# Dragon_LowerCase_v1.net
KiCad netlist of a schematic drawn in EAGLE
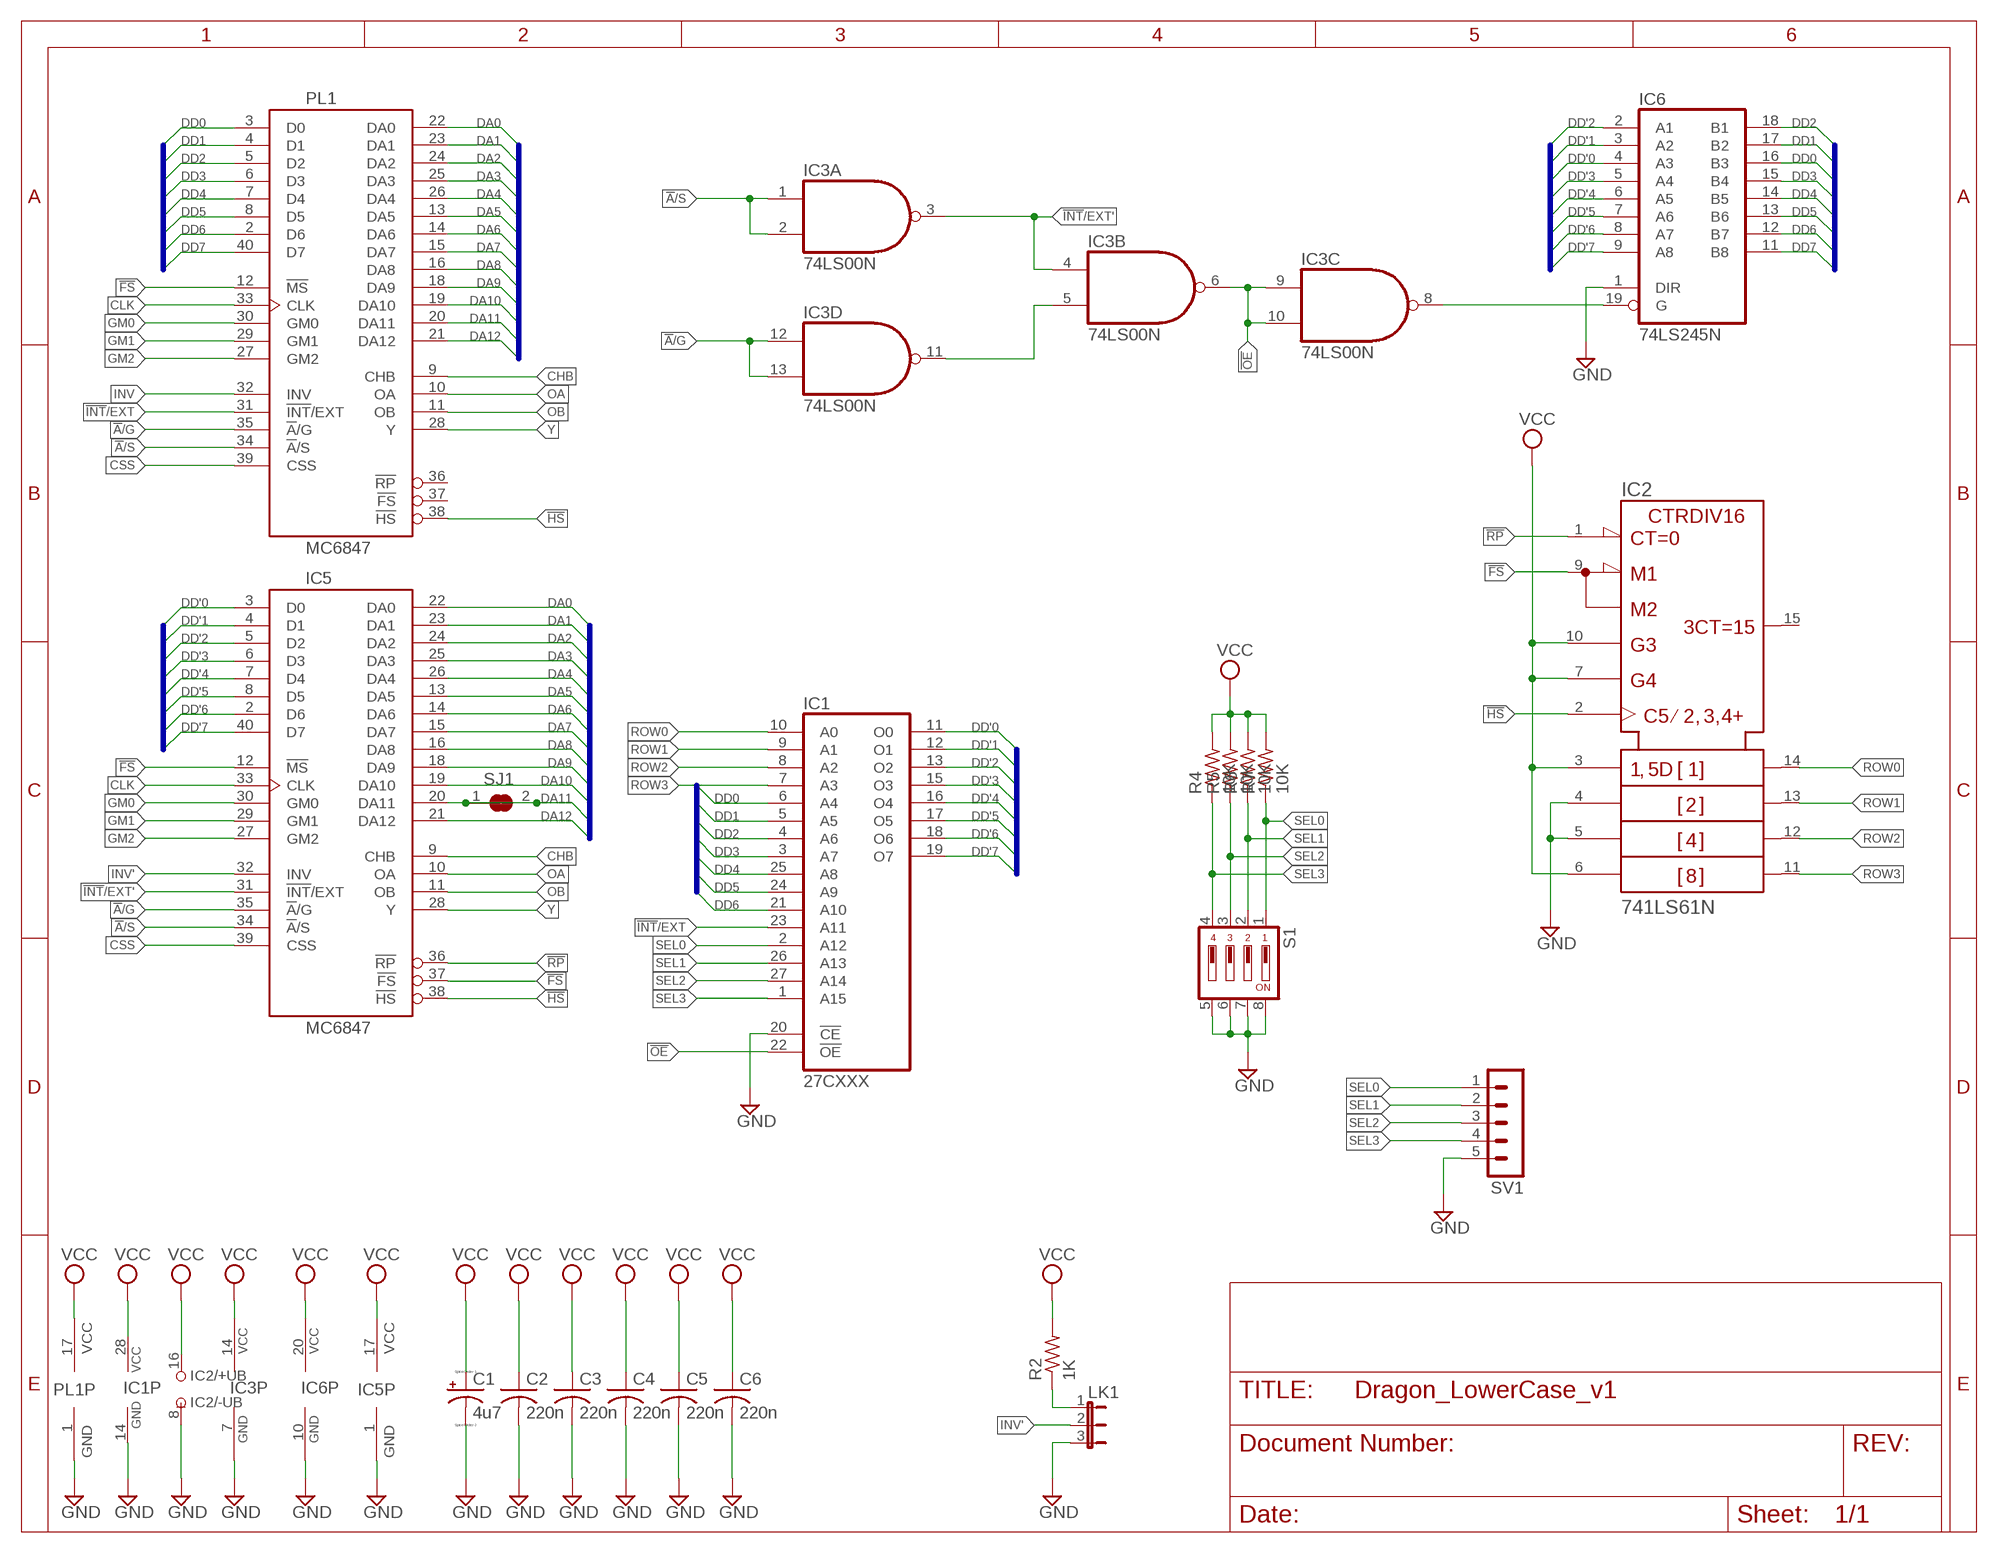
[diagram p0: schematic, sheet 1]

(export (version "E")
  (design (tool "Eeschema 10.0.6"))
  (components
    (comp (ref "C1")
      (value "4u7")
      (footprint "eagle-import:E2,5-5")
      (libsource (lib "eagle-import") (part "CPOL-USE2.5-5"))
    )
    (comp (ref "C2")
      (value "220n")
      (footprint "eagle-import:C025-025X050")
      (libsource (lib "eagle-import") (part "C-US025-025X050"))
    )
    (comp (ref "C3")
      (value "220n")
      (footprint "eagle-import:C025-025X050")
      (libsource (lib "eagle-import") (part "C-US025-025X050"))
    )
    (comp (ref "C4")
      (value "220n")
      (footprint "eagle-import:C025-025X050")
      (libsource (lib "eagle-import") (part "C-US025-025X050"))
    )
    (comp (ref "C5")
      (value "220n")
      (footprint "eagle-import:C050-025X075")
      (libsource (lib "eagle-import") (part "C-US050-025X075"))
    )
    (comp (ref "C6")
      (value "220n")
      (footprint "eagle-import:C025-025X050")
      (libsource (lib "eagle-import") (part "C-US025-025X050"))
    )
    (comp (ref "IC1")
      (value "27CXXX")
      (footprint "eagle-import:DIL28")
      (libsource (lib "eagle-import") (part "27512"))
    )
    (comp (ref "IC2")
      (value "741LS61N")
      (footprint "eagle-import:DIL16")
      (libsource (lib "eagle-import") (part "74161N"))
    )
    (comp (ref "IC3")
      (value "74LS00N")
      (footprint "eagle-import:DIL14-RP")
      (libsource (lib "eagle-import") (part "7400NLS"))
    )
    (comp (ref "IC5")
      (value "MC6847")
      (footprint "eagle-import:DIL40")
      (libsource (lib "eagle-import") (part "MC6847"))
    )
    (comp (ref "IC6")
      (value "74LS245N")
      (footprint "eagle-import:DIL20-RP")
      (libsource (lib "eagle-import") (part "74245NLS"))
    )
    (comp (ref "LK1")
      (value "JP2E")
      (footprint "eagle-import:JP2")
      (libsource (lib "eagle-import") (part "JP2E"))
    )
    (comp (ref "PL1")
      (value "MC6847")
      (footprint "eagle-import:DIL40")
      (libsource (lib "eagle-import") (part "MC6847"))
    )
    (comp (ref "R2")
      (value "1K")
      (footprint "eagle-import:0204V")
      (libsource (lib "eagle-import") (part "R-US_0204/2V"))
    )
    (comp (ref "R4")
      (value "10K")
      (footprint "eagle-import:0204V")
      (libsource (lib "eagle-import") (part "R-US_0204/2V"))
    )
    (comp (ref "R5")
      (value "10K")
      (footprint "eagle-import:0204V")
      (libsource (lib "eagle-import") (part "R-US_0204/2V"))
    )
    (comp (ref "R6")
      (value "10K")
      (footprint "eagle-import:0204V")
      (libsource (lib "eagle-import") (part "R-US_0204/2V"))
    )
    (comp (ref "R7")
      (value "10K")
      (footprint "eagle-import:0204V")
      (libsource (lib "eagle-import") (part "R-US_0204/2V"))
    )
    (comp (ref "S1")
      (value "DS04")
      (footprint "eagle-import:DS-04")
      (libsource (lib "eagle-import") (part "DS04"))
    )
    (comp (ref "SJ1") (value "SJ") (footprint "eagle-import:SJ") (libsource (lib "eagle-import") (part "SJ")))
    (comp (ref "SV1")
      (value "MA05-1")
      (footprint "eagle-import:MA05-1")
      (libsource (lib "eagle-import") (part "MA05-1"))
    )
  )
  (nets
    (net (code "1") (name "/DA0") (class "Default")
      (node (ref "IC5") (pin "22") (pinfunction "DA0_22") (pintype "output"))
      (node (ref "PL1") (pin "22") (pinfunction "DA0_22") (pintype "output"))
    )
    (net (code "2") (name "/DA1") (class "Default")
      (node (ref "IC5") (pin "23") (pinfunction "DA1_23") (pintype "output"))
      (node (ref "PL1") (pin "23") (pinfunction "DA1_23") (pintype "output"))
    )
    (net (code "3") (name "/DA2") (class "Default")
      (node (ref "IC5") (pin "24") (pinfunction "DA2_24") (pintype "output"))
      (node (ref "PL1") (pin "24") (pinfunction "DA2_24") (pintype "output"))
    )
    (net (code "4") (name "/DA3") (class "Default")
      (node (ref "IC5") (pin "25") (pinfunction "DA3_25") (pintype "output"))
      (node (ref "PL1") (pin "25") (pinfunction "DA3_25") (pintype "output"))
    )
    (net (code "5") (name "/DA4") (class "Default")
      (node (ref "IC5") (pin "26") (pinfunction "DA4_26") (pintype "output"))
      (node (ref "PL1") (pin "26") (pinfunction "DA4_26") (pintype "output"))
    )
    (net (code "6") (name "/DA5") (class "Default")
      (node (ref "IC5") (pin "13") (pinfunction "DA5_13") (pintype "output"))
      (node (ref "PL1") (pin "13") (pinfunction "DA5_13") (pintype "output"))
    )
    (net (code "7") (name "/DA6") (class "Default")
      (node (ref "IC5") (pin "14") (pinfunction "DA6_14") (pintype "output"))
      (node (ref "PL1") (pin "14") (pinfunction "DA6_14") (pintype "output"))
    )
    (net (code "8") (name "/DA7") (class "Default")
      (node (ref "IC5") (pin "15") (pinfunction "DA7_15") (pintype "output"))
      (node (ref "PL1") (pin "15") (pinfunction "DA7_15") (pintype "output"))
    )
    (net (code "9") (name "/DA8") (class "Default")
      (node (ref "IC5") (pin "16") (pinfunction "DA8_16") (pintype "output"))
      (node (ref "PL1") (pin "16") (pinfunction "DA8_16") (pintype "output"))
    )
    (net (code "10") (name "/DA9") (class "Default")
      (node (ref "IC5") (pin "18") (pinfunction "DA9_18") (pintype "output"))
      (node (ref "PL1") (pin "18") (pinfunction "DA9_18") (pintype "output"))
    )
    (net (code "11") (name "/DA10") (class "Default")
      (node (ref "IC5") (pin "19") (pinfunction "DA10_19") (pintype "output"))
      (node (ref "PL1") (pin "19") (pinfunction "DA10_19") (pintype "output"))
    )
    (net (code "12") (name "/DA11") (class "Default")
      (node (ref "IC5") (pin "20") (pinfunction "DA11_20") (pintype "output"))
      (node (ref "PL1") (pin "20") (pinfunction "DA11_20") (pintype "output"))
      (node (ref "SJ1") (pin "1") (pinfunction "1_1") (pintype "passive"))
      (node (ref "SJ1") (pin "2") (pinfunction "2_2") (pintype "passive"))
    )
    (net (code "13") (name "/DA12") (class "Default")
      (node (ref "IC5") (pin "21") (pinfunction "DA12_21") (pintype "output"))
      (node (ref "PL1") (pin "21") (pinfunction "DA12_21") (pintype "output"))
    )
    (net (code "14") (name "/DD'0") (class "Default")
      (node (ref "IC1") (pin "11") (pinfunction "O0_11") (pintype "tri_state"))
      (node (ref "IC5") (pin "3") (pinfunction "D0_3") (pintype "input"))
      (node (ref "IC6") (pin "4") (pinfunction "A3_4") (pintype "bidirectional"))
    )
    (net (code "15") (name "/DD'1") (class "Default")
      (node (ref "IC1") (pin "12") (pinfunction "O1_12") (pintype "tri_state"))
      (node (ref "IC5") (pin "4") (pinfunction "D1_4") (pintype "input"))
      (node (ref "IC6") (pin "3") (pinfunction "A2_3") (pintype "bidirectional"))
    )
    (net (code "16") (name "/DD'2") (class "Default")
      (node (ref "IC1") (pin "13") (pinfunction "O2_13") (pintype "tri_state"))
      (node (ref "IC5") (pin "5") (pinfunction "D2_5") (pintype "input"))
      (node (ref "IC6") (pin "2") (pinfunction "A1_2") (pintype "bidirectional"))
    )
    (net (code "17") (name "/DD'3") (class "Default")
      (node (ref "IC1") (pin "15") (pinfunction "O3_15") (pintype "tri_state"))
      (node (ref "IC5") (pin "6") (pinfunction "D3_6") (pintype "input"))
      (node (ref "IC6") (pin "5") (pinfunction "A4_5") (pintype "bidirectional"))
    )
    (net (code "18") (name "/DD'4") (class "Default")
      (node (ref "IC1") (pin "16") (pinfunction "O4_16") (pintype "tri_state"))
      (node (ref "IC5") (pin "7") (pinfunction "D4_7") (pintype "input"))
      (node (ref "IC6") (pin "6") (pinfunction "A5_6") (pintype "bidirectional"))
    )
    (net (code "19") (name "/DD'5") (class "Default")
      (node (ref "IC1") (pin "17") (pinfunction "O5_17") (pintype "tri_state"))
      (node (ref "IC5") (pin "8") (pinfunction "D5_8") (pintype "input"))
      (node (ref "IC6") (pin "7") (pinfunction "A6_7") (pintype "bidirectional"))
    )
    (net (code "20") (name "/DD'6") (class "Default")
      (node (ref "IC1") (pin "18") (pinfunction "O6_18") (pintype "tri_state"))
      (node (ref "IC5") (pin "2") (pinfunction "D6_2") (pintype "input"))
      (node (ref "IC6") (pin "8") (pinfunction "A7_8") (pintype "bidirectional"))
    )
    (net (code "21") (name "/DD'7") (class "Default")
      (node (ref "IC1") (pin "19") (pinfunction "O7_19") (pintype "tri_state"))
      (node (ref "IC5") (pin "40") (pinfunction "D7_40") (pintype "input"))
      (node (ref "IC6") (pin "9") (pinfunction "A8_9") (pintype "bidirectional"))
    )
    (net (code "22") (name "/DD0") (class "Default")
      (node (ref "IC1") (pin "6") (pinfunction "A4_6") (pintype "input"))
      (node (ref "IC6") (pin "16") (pinfunction "B3_16") (pintype "bidirectional"))
      (node (ref "PL1") (pin "3") (pinfunction "D0_3") (pintype "input"))
    )
    (net (code "23") (name "/DD1") (class "Default")
      (node (ref "IC1") (pin "5") (pinfunction "A5_5") (pintype "input"))
      (node (ref "IC6") (pin "17") (pinfunction "B2_17") (pintype "bidirectional"))
      (node (ref "PL1") (pin "4") (pinfunction "D1_4") (pintype "input"))
    )
    (net (code "24") (name "/DD2") (class "Default")
      (node (ref "IC1") (pin "4") (pinfunction "A6_4") (pintype "input"))
      (node (ref "IC6") (pin "18") (pinfunction "B1_18") (pintype "bidirectional"))
      (node (ref "PL1") (pin "5") (pinfunction "D2_5") (pintype "input"))
    )
    (net (code "25") (name "/DD3") (class "Default")
      (node (ref "IC1") (pin "3") (pinfunction "A7_3") (pintype "input"))
      (node (ref "IC6") (pin "15") (pinfunction "B4_15") (pintype "bidirectional"))
      (node (ref "PL1") (pin "6") (pinfunction "D3_6") (pintype "input"))
    )
    (net (code "26") (name "/DD4") (class "Default")
      (node (ref "IC1") (pin "25") (pinfunction "A8_25") (pintype "input"))
      (node (ref "IC6") (pin "14") (pinfunction "B5_14") (pintype "bidirectional"))
      (node (ref "PL1") (pin "7") (pinfunction "D4_7") (pintype "input"))
    )
    (net (code "27") (name "/DD5") (class "Default")
      (node (ref "IC1") (pin "24") (pinfunction "A9_24") (pintype "input"))
      (node (ref "IC6") (pin "13") (pinfunction "B6_13") (pintype "bidirectional"))
      (node (ref "PL1") (pin "8") (pinfunction "D5_8") (pintype "input"))
    )
    (net (code "28") (name "/DD6") (class "Default")
      (node (ref "IC1") (pin "21") (pinfunction "A10_21") (pintype "input"))
      (node (ref "IC6") (pin "12") (pinfunction "B7_12") (pintype "bidirectional"))
      (node (ref "PL1") (pin "2") (pinfunction "D6_2") (pintype "input"))
    )
    (net (code "29") (name "/DD7") (class "Default")
      (node (ref "IC6") (pin "11") (pinfunction "B8_11") (pintype "bidirectional"))
      (node (ref "PL1") (pin "40") (pinfunction "D7_40") (pintype "input"))
    )
    (net (code "30") (name "/~{A}{slash}G") (class "Default")
      (node (ref "IC3") (pin "12") (pinfunction "I0_12") (pintype "input"))
      (node (ref "IC3") (pin "13") (pinfunction "I1_13") (pintype "input"))
      (node (ref "IC5") (pin "35") (pinfunction "~{A}/G_35") (pintype "input"))
      (node (ref "PL1") (pin "35") (pinfunction "~{A}/G_35") (pintype "input"))
    )
    (net (code "31") (name "/~{A}{slash}S") (class "Default")
      (node (ref "IC3") (pin "1") (pinfunction "I0_1") (pintype "input"))
      (node (ref "IC3") (pin "2") (pinfunction "I1_2") (pintype "input"))
      (node (ref "IC5") (pin "34") (pinfunction "~{A}/S_34") (pintype "input"))
      (node (ref "PL1") (pin "34") (pinfunction "~{A}/S_34") (pintype "input"))
    )
    (net (code "32") (name "/~{FS}") (class "Default")
      (node (ref "IC2") (pin "9") (pinfunction "~{LOAD}_9") (pintype "input"))
      (node (ref "IC5") (pin "12") (pinfunction "~{MS}_12") (pintype "input"))
      (node (ref "IC5") (pin "37") (pinfunction "~{FS}_37") (pintype "output"))
      (node (ref "PL1") (pin "12") (pinfunction "~{MS}_12") (pintype "input"))
    )
    (net (code "33") (name "/~{HS}") (class "Default")
      (node (ref "IC2") (pin "2") (pinfunction "CLK_2") (pintype "input"))
      (node (ref "IC5") (pin "38") (pinfunction "~{HS}_38") (pintype "output"))
      (node (ref "PL1") (pin "38") (pinfunction "~{HS}_38") (pintype "output"))
    )
    (net (code "34") (name "/~{INT}{slash}EXT") (class "Default")
      (node (ref "IC1") (pin "23") (pinfunction "A11_23") (pintype "input"))
      (node (ref "PL1") (pin "31") (pinfunction "~{INT}/EXT_31") (pintype "input"))
    )
    (net (code "35") (name "/~{INT}{slash}EXT'") (class "Default")
      (node (ref "IC3") (pin "3") (pinfunction "O_3") (pintype "output"))
      (node (ref "IC3") (pin "4") (pinfunction "I0_4") (pintype "input"))
      (node (ref "IC5") (pin "31") (pinfunction "~{INT}/EXT_31") (pintype "input"))
    )
    (net (code "36") (name "/~{OE}") (class "Default")
      (node (ref "IC1") (pin "22") (pinfunction "~{OE}_22") (pintype "input"))
      (node (ref "IC3") (pin "10") (pinfunction "I1_10") (pintype "input"))
      (node (ref "IC3") (pin "6") (pinfunction "O_6") (pintype "output"))
      (node (ref "IC3") (pin "9") (pinfunction "I0_9") (pintype "input"))
    )
    (net (code "37") (name "/~{RP}") (class "Default")
      (node (ref "IC2") (pin "1") (pinfunction "~{CLR}_1") (pintype "input"))
      (node (ref "IC5") (pin "36") (pinfunction "~{RP}_36") (pintype "output"))
    )
    (net (code "38") (name "CHB") (class "Default")
      (node (ref "IC5") (pin "9") (pinfunction "CHB_9") (pintype "output"))
      (node (ref "PL1") (pin "9") (pinfunction "CHB_9") (pintype "output"))
    )
    (net (code "39") (name "CLK") (class "Default")
      (node (ref "IC5") (pin "33") (pinfunction "CLK_33") (pintype "input"))
      (node (ref "PL1") (pin "33") (pinfunction "CLK_33") (pintype "input"))
    )
    (net (code "40") (name "CSS") (class "Default")
      (node (ref "IC5") (pin "39") (pinfunction "CSS_39") (pintype "input"))
      (node (ref "PL1") (pin "39") (pinfunction "CSS_39") (pintype "input"))
    )
    (net (code "41") (name "GM0") (class "Default")
      (node (ref "IC5") (pin "30") (pinfunction "GM0_30") (pintype "input"))
      (node (ref "PL1") (pin "30") (pinfunction "GM0_30") (pintype "input"))
    )
    (net (code "42") (name "GM1") (class "Default")
      (node (ref "IC5") (pin "29") (pinfunction "GM1_29") (pintype "input"))
      (node (ref "PL1") (pin "29") (pinfunction "GM1_29") (pintype "input"))
    )
    (net (code "43") (name "GM2") (class "Default")
      (node (ref "IC5") (pin "27") (pinfunction "GM2_27") (pintype "input"))
      (node (ref "PL1") (pin "27") (pinfunction "GM2_27") (pintype "input"))
    )
    (net (code "44") (name "GND") (class "Default")
      (node (ref "C1") (pin "-") (pinfunction "-_-") (pintype "passive"))
      (node (ref "C2") (pin "2") (pinfunction "2_2") (pintype "passive"))
      (node (ref "C3") (pin "2") (pinfunction "2_2") (pintype "passive"))
      (node (ref "C4") (pin "2") (pinfunction "2_2") (pintype "passive"))
      (node (ref "C5") (pin "2") (pinfunction "2_2") (pintype "passive"))
      (node (ref "C6") (pin "2") (pinfunction "2_2") (pintype "passive"))
      (node (ref "IC1") (pin "14") (pinfunction "GND_14") (pintype "power_in"))
      (node (ref "IC1") (pin "20") (pinfunction "~{CE}_20") (pintype "input"))
      (node (ref "IC2") (pin "4") (pinfunction "B_4") (pintype "input"))
      (node (ref "IC2") (pin "5") (pinfunction "C_5") (pintype "input"))
      (node (ref "IC2") (pin "8") (pinfunction "-UB_8") (pintype "power_in"))
      (node (ref "IC3") (pin "7") (pinfunction "GND_7") (pintype "power_in"))
      (node (ref "IC5") (pin "1") (pinfunction "GND_1") (pintype "power_in"))
      (node (ref "IC6") (pin "1") (pinfunction "DIR_1") (pintype "input"))
      (node (ref "IC6") (pin "10") (pinfunction "GND_10") (pintype "power_in"))
      (node (ref "LK1") (pin "3") (pinfunction "3_3") (pintype "passive"))
      (node (ref "PL1") (pin "1") (pinfunction "GND_1") (pintype "power_in"))
      (node (ref "S1") (pin "5") (pinfunction "5_5") (pintype "passive"))
      (node (ref "S1") (pin "6") (pinfunction "6_6") (pintype "passive"))
      (node (ref "S1") (pin "7") (pinfunction "7_7") (pintype "passive"))
      (node (ref "S1") (pin "8") (pinfunction "8_8") (pintype "passive"))
      (node (ref "SV1") (pin "5") (pinfunction "5_5") (pintype "passive"))
    )
    (net (code "45") (name "INV") (class "Default")
      (node (ref "PL1") (pin "32") (pinfunction "INV_32") (pintype "input"))
    )
    (net (code "46") (name "INV'") (class "Default")
      (node (ref "IC5") (pin "32") (pinfunction "INV_32") (pintype "input"))
      (node (ref "LK1") (pin "2") (pinfunction "2_2") (pintype "passive"))
    )
    (net (code "47") (name "Net-(IC3B-I1)") (class "Default")
      (node (ref "IC3") (pin "11") (pinfunction "O_11") (pintype "output"))
      (node (ref "IC3") (pin "5") (pinfunction "I1_5") (pintype "input"))
    )
    (net (code "48") (name "Net-(IC3C-O)") (class "Default")
      (node (ref "IC3") (pin "8") (pinfunction "O_8") (pintype "output"))
      (node (ref "IC6") (pin "19") (pinfunction "G_19") (pintype "input"))
    )
    (net (code "49") (name "Net-(LK1-Pad1)") (class "Default")
      (node (ref "LK1") (pin "1") (pinfunction "1_1") (pintype "passive"))
      (node (ref "R2") (pin "1") (pinfunction "1_1") (pintype "passive"))
    )
    (net (code "50") (name "OA") (class "Default")
      (node (ref "IC5") (pin "10") (pinfunction "OA_10") (pintype "output"))
      (node (ref "PL1") (pin "10") (pinfunction "OA_10") (pintype "output"))
    )
    (net (code "51") (name "OB") (class "Default")
      (node (ref "IC5") (pin "11") (pinfunction "OB_11") (pintype "output"))
      (node (ref "PL1") (pin "11") (pinfunction "OB_11") (pintype "output"))
    )
    (net (code "52") (name "ROW0") (class "Default")
      (node (ref "IC1") (pin "10") (pinfunction "A0_10") (pintype "input"))
      (node (ref "IC2") (pin "14") (pinfunction "QA_14") (pintype "output"))
    )
    (net (code "53") (name "ROW1") (class "Default")
      (node (ref "IC1") (pin "9") (pinfunction "A1_9") (pintype "input"))
      (node (ref "IC2") (pin "13") (pinfunction "QB_13") (pintype "output"))
    )
    (net (code "54") (name "ROW2") (class "Default")
      (node (ref "IC1") (pin "8") (pinfunction "A2_8") (pintype "input"))
      (node (ref "IC2") (pin "12") (pinfunction "QC_12") (pintype "output"))
    )
    (net (code "55") (name "ROW3") (class "Default")
      (node (ref "IC1") (pin "7") (pinfunction "A3_7") (pintype "input"))
      (node (ref "IC2") (pin "11") (pinfunction "QD_11") (pintype "output"))
    )
    (net (code "56") (name "SEL0") (class "Default")
      (node (ref "IC1") (pin "2") (pinfunction "A12_2") (pintype "input"))
      (node (ref "R7") (pin "1") (pinfunction "1_1") (pintype "passive"))
      (node (ref "S1") (pin "1") (pinfunction "1_1") (pintype "passive"))
      (node (ref "SV1") (pin "1") (pinfunction "1_1") (pintype "passive"))
    )
    (net (code "57") (name "SEL1") (class "Default")
      (node (ref "IC1") (pin "26") (pinfunction "A13_26") (pintype "input"))
      (node (ref "R6") (pin "1") (pinfunction "1_1") (pintype "passive"))
      (node (ref "S1") (pin "2") (pinfunction "2_2") (pintype "passive"))
      (node (ref "SV1") (pin "2") (pinfunction "2_2") (pintype "passive"))
    )
    (net (code "58") (name "SEL2") (class "Default")
      (node (ref "IC1") (pin "27") (pinfunction "A14_27") (pintype "input"))
      (node (ref "R5") (pin "1") (pinfunction "1_1") (pintype "passive"))
      (node (ref "S1") (pin "3") (pinfunction "3_3") (pintype "passive"))
      (node (ref "SV1") (pin "3") (pinfunction "3_3") (pintype "passive"))
    )
    (net (code "59") (name "SEL3") (class "Default")
      (node (ref "IC1") (pin "1") (pinfunction "A15_1") (pintype "input"))
      (node (ref "R4") (pin "1") (pinfunction "1_1") (pintype "passive"))
      (node (ref "S1") (pin "4") (pinfunction "4_4") (pintype "passive"))
      (node (ref "SV1") (pin "4") (pinfunction "4_4") (pintype "passive"))
    )
    (net (code "60") (name "VCC") (class "Default")
      (node (ref "C1") (pin "+") (pinfunction "+_+") (pintype "passive"))
      (node (ref "C2") (pin "1") (pinfunction "1_1") (pintype "passive"))
      (node (ref "C3") (pin "1") (pinfunction "1_1") (pintype "passive"))
      (node (ref "C4") (pin "1") (pinfunction "1_1") (pintype "passive"))
      (node (ref "C5") (pin "1") (pinfunction "1_1") (pintype "passive"))
      (node (ref "C6") (pin "1") (pinfunction "1_1") (pintype "passive"))
      (node (ref "IC1") (pin "28") (pinfunction "VCC_28") (pintype "power_in"))
      (node (ref "IC2") (pin "10") (pinfunction "ENT_10") (pintype "input"))
      (node (ref "IC2") (pin "16") (pinfunction "+UB_16") (pintype "power_in"))
      (node (ref "IC2") (pin "3") (pinfunction "A_3") (pintype "input"))
      (node (ref "IC2") (pin "6") (pinfunction "D_6") (pintype "input"))
      (node (ref "IC2") (pin "7") (pinfunction "ENP_7") (pintype "input"))
      (node (ref "IC3") (pin "14") (pinfunction "VCC_14") (pintype "power_in"))
      (node (ref "IC5") (pin "17") (pinfunction "VCC_17") (pintype "power_in"))
      (node (ref "IC6") (pin "20") (pinfunction "VCC_20") (pintype "power_in"))
      (node (ref "PL1") (pin "17") (pinfunction "VCC_17") (pintype "power_in"))
      (node (ref "R2") (pin "2") (pinfunction "2_2") (pintype "passive"))
      (node (ref "R4") (pin "2") (pinfunction "2_2") (pintype "passive"))
      (node (ref "R5") (pin "2") (pinfunction "2_2") (pintype "passive"))
      (node (ref "R6") (pin "2") (pinfunction "2_2") (pintype "passive"))
      (node (ref "R7") (pin "2") (pinfunction "2_2") (pintype "passive"))
    )
    (net (code "61") (name "Y") (class "Default")
      (node (ref "IC5") (pin "28") (pinfunction "Y_28") (pintype "output"))
      (node (ref "PL1") (pin "28") (pinfunction "Y_28") (pintype "output"))
    )
    (net (code "62") (name "unconnected-(IC2C-RCO-Pad15)") (class "Default")
      (node (ref "IC2") (pin "15") (pinfunction "RCO_15") (pintype "output"))
    )
    (net (code "63") (name "unconnected-(PL1A-~{FS}-Pad37)") (class "Default")
      (node (ref "PL1") (pin "37") (pinfunction "~{FS}_37") (pintype "output"))
    )
    (net (code "64") (name "unconnected-(PL1A-~{RP}-Pad36)") (class "Default")
      (node (ref "PL1") (pin "36") (pinfunction "~{RP}_36") (pintype "output"))
    )
  )
)
